# CF_ADC_Supply.net
KiCad netlist of a schematic drawn in Altium Designer
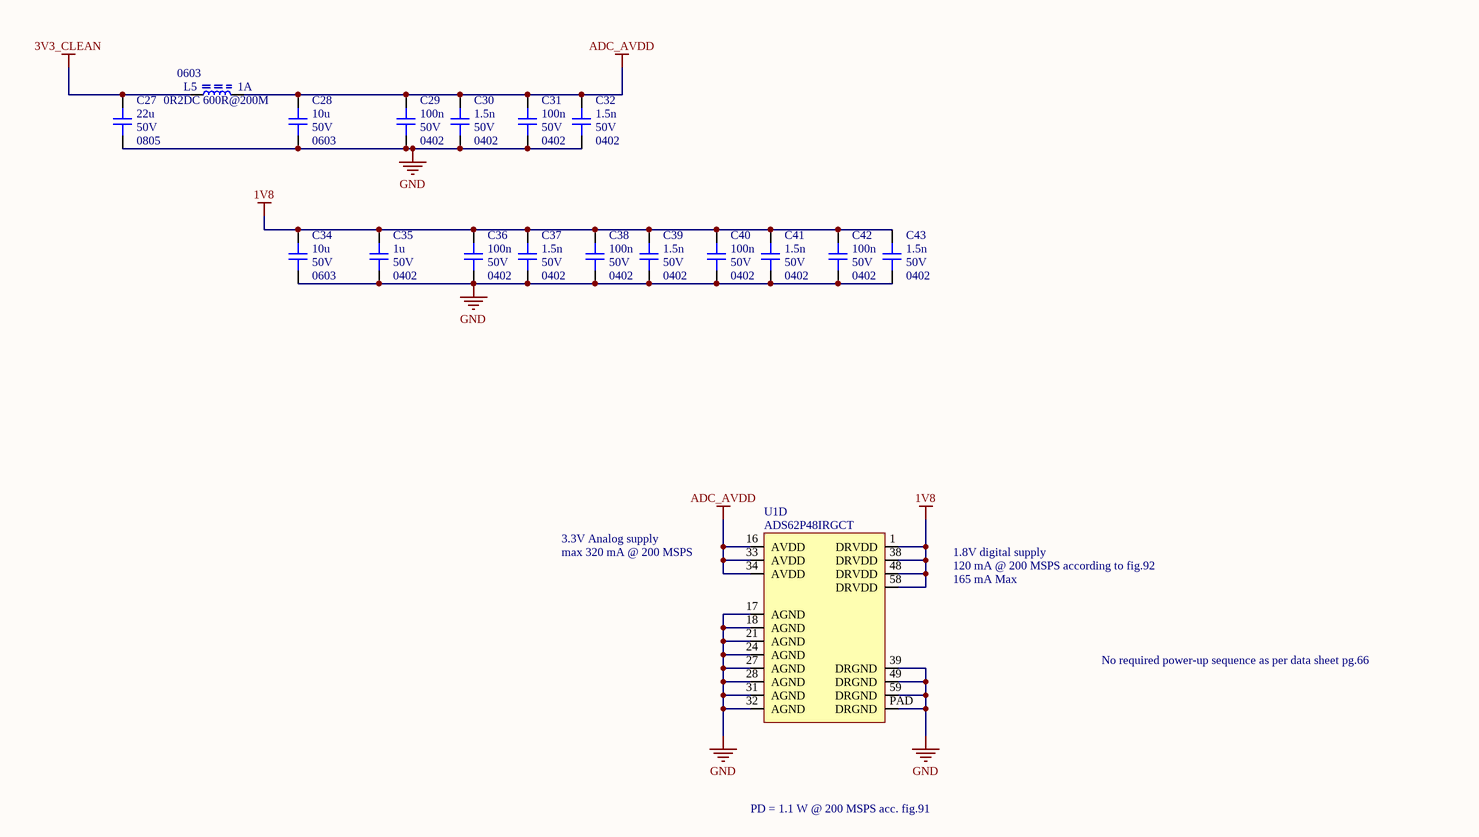
[diagram p0: CF_ADC_Supply.SchDoc]

(export (version "E")
  (design (tool "Eeschema 10.0.6"))
  (components
    (comp (ref "C27")
      (value "22u")
      (footprint "CAP_0805")
      (description "CAP - 0805")
      (fields
        (field (name "VOLTAGE") "50V")
        (field (name "PACKAGE") "0805")
        (field (name "CREATEDBY") "Jonathan Bouchard")
      )
      (libsource (lib "S7CAS_Lib2019_REV1_00") (part "CAP - 0805"))
    )
    (comp (ref "C28")
      (value "10u")
      (footprint "CAP_0603")
      (description "CAP - 0603")
      (fields
        (field (name "MFG PART NUMBER") "C1005X5R0J106M050BC")
        (field (name "VOLTAGE") "50V")
        (field (name "PACKAGE") "0603")
        (field (name "CREATEDBY") "Jonathan Bouchard")
      )
      (libsource (lib "S7CAS_Lib2019_REV1_00") (part "CAP - 0603"))
    )
    (comp (ref "C29")
      (value "100n")
      (footprint "CAP_0402")
      (description "CAP - 0402")
      (fields
        (field (name "MFG PART NUMBER") "C0603X5R1E104K030BB")
        (field (name "VOLTAGE") "50V")
        (field (name "PACKAGE") "0402")
        (field (name "CREATEDBY") "Jonathan Bouchard")
      )
      (libsource (lib "S7CAS_Lib2019_REV1_00") (part "CAP - 0402"))
    )
    (comp (ref "C30")
      (value "1.5n")
      (footprint "CAP_0402")
      (description "CAP - 0402")
      (fields
        (field (name "MFG PART NUMBER") "C0603X5R1E152M030BA")
        (field (name "VOLTAGE") "50V")
        (field (name "PACKAGE") "0402")
        (field (name "CREATEDBY") "Jonathan Bouchard")
      )
      (libsource (lib "S7CAS_Lib2019_REV1_00") (part "CAP - 0402"))
    )
    (comp (ref "C31")
      (value "100n")
      (footprint "CAP_0402")
      (description "CAP - 0402")
      (fields
        (field (name "MFG PART NUMBER") "C0603X5R1E104K030BB")
        (field (name "VOLTAGE") "50V")
        (field (name "PACKAGE") "0402")
        (field (name "CREATEDBY") "Jonathan Bouchard")
      )
      (libsource (lib "S7CAS_Lib2019_REV1_00") (part "CAP - 0402"))
    )
    (comp (ref "C32")
      (value "1.5n")
      (footprint "CAP_0402")
      (description "CAP - 0402")
      (fields
        (field (name "MFG PART NUMBER") "C0603X5R1E152M030BA")
        (field (name "VOLTAGE") "50V")
        (field (name "PACKAGE") "0402")
        (field (name "CREATEDBY") "Jonathan Bouchard")
      )
      (libsource (lib "S7CAS_Lib2019_REV1_00") (part "CAP - 0402"))
    )
    (comp (ref "C34")
      (value "10u")
      (footprint "CAP_0603")
      (description "CAP - 0603")
      (fields
        (field (name "MFG PART NUMBER") "C1005X5R0J106M050BC")
        (field (name "VOLTAGE") "50V")
        (field (name "PACKAGE") "0603")
        (field (name "CREATEDBY") "Jonathan Bouchard")
      )
      (libsource (lib "S7CAS_Lib2019_REV1_00") (part "CAP - 0603"))
    )
    (comp (ref "C35")
      (value "1u")
      (footprint "CAP_0402")
      (description "CAP - 0402")
      (fields
        (field (name "MFG PART NUMBER") "C0603X5R0J105M030BC")
        (field (name "VOLTAGE") "50V")
        (field (name "PACKAGE") "0402")
        (field (name "CREATEDBY") "Jonathan Bouchard")
      )
      (libsource (lib "S7CAS_Lib2019_REV1_00") (part "CAP - 0402"))
    )
    (comp (ref "C36")
      (value "100n")
      (footprint "CAP_0402")
      (description "CAP - 0402")
      (fields
        (field (name "MFG PART NUMBER") "C0603X5R1E104K030BB")
        (field (name "VOLTAGE") "50V")
        (field (name "PACKAGE") "0402")
        (field (name "CREATEDBY") "Jonathan Bouchard")
      )
      (libsource (lib "S7CAS_Lib2019_REV1_00") (part "CAP - 0402"))
    )
    (comp (ref "C37")
      (value "1.5n")
      (footprint "CAP_0402")
      (description "CAP - 0402")
      (fields
        (field (name "MFG PART NUMBER") "C0603X5R1E152M030BA")
        (field (name "VOLTAGE") "50V")
        (field (name "PACKAGE") "0402")
        (field (name "CREATEDBY") "Jonathan Bouchard")
      )
      (libsource (lib "S7CAS_Lib2019_REV1_00") (part "CAP - 0402"))
    )
    (comp (ref "C38")
      (value "100n")
      (footprint "CAP_0402")
      (description "CAP - 0402")
      (fields
        (field (name "MFG PART NUMBER") "C0603X5R1E104K030BB")
        (field (name "VOLTAGE") "50V")
        (field (name "PACKAGE") "0402")
        (field (name "CREATEDBY") "Jonathan Bouchard")
      )
      (libsource (lib "S7CAS_Lib2019_REV1_00") (part "CAP - 0402"))
    )
    (comp (ref "C39")
      (value "1.5n")
      (footprint "CAP_0402")
      (description "CAP - 0402")
      (fields
        (field (name "MFG PART NUMBER") "C0603X5R1E152M030BA")
        (field (name "VOLTAGE") "50V")
        (field (name "PACKAGE") "0402")
        (field (name "CREATEDBY") "Jonathan Bouchard")
      )
      (libsource (lib "S7CAS_Lib2019_REV1_00") (part "CAP - 0402"))
    )
    (comp (ref "C40")
      (value "100n")
      (footprint "CAP_0402")
      (description "CAP - 0402")
      (fields
        (field (name "MFG PART NUMBER") "C0603X5R1E104K030BB")
        (field (name "VOLTAGE") "50V")
        (field (name "PACKAGE") "0402")
        (field (name "CREATEDBY") "Jonathan Bouchard")
      )
      (libsource (lib "S7CAS_Lib2019_REV1_00") (part "CAP - 0402"))
    )
    (comp (ref "C41")
      (value "1.5n")
      (footprint "CAP_0402")
      (description "CAP - 0402")
      (fields
        (field (name "MFG PART NUMBER") "C0603X5R1E152M030BA")
        (field (name "VOLTAGE") "50V")
        (field (name "PACKAGE") "0402")
        (field (name "CREATEDBY") "Jonathan Bouchard")
      )
      (libsource (lib "S7CAS_Lib2019_REV1_00") (part "CAP - 0402"))
    )
    (comp (ref "C42")
      (value "100n")
      (footprint "CAP_0402")
      (description "CAP - 0402")
      (fields
        (field (name "MFG PART NUMBER") "C0603X5R1E104K030BB")
        (field (name "VOLTAGE") "50V")
        (field (name "PACKAGE") "0402")
        (field (name "CREATEDBY") "Jonathan Bouchard")
      )
      (libsource (lib "S7CAS_Lib2019_REV1_00") (part "CAP - 0402"))
    )
    (comp (ref "C43")
      (value "1.5n")
      (footprint "CAP_0402")
      (description "CAP - 0402")
      (fields
        (field (name "MFG PART NUMBER") "C0603X5R1E152M030BA")
        (field (name "VOLTAGE") "50V")
        (field (name "PACKAGE") "0402")
        (field (name "CREATEDBY") "Jonathan Bouchard")
      )
      (libsource (lib "S7CAS_Lib2019_REV1_00") (part "CAP - 0402"))
    )
    (comp (ref "L5")
      (value "0R2DC 600R@200M")
      (footprint "FER_0603")
      (description "FER - 0603")
      (fields
        (field (name "MFG") "Würth Elektronik")
        (field (name "MFG PART NUMBER") "782633601")
        (field (name "CURRENT") "1A")
        (field (name "PACKAGE") "0603")
        (field (name "CREATEDBY") "Jonathan Bouchard")
      )
      (libsource (lib "S7CAS_Lib2019_REV1_00") (part "FER - 0603"))
    )
    (comp (ref "U1")
      (value "ADS62P48IRGCT")
      (footprint "ADC_ADS62P48IRGCT")
      (description "ADC - 14 BIT 210MSPS SUAL - VQFN-64")
      (fields
        (field (name "VOLTAGE") "3.15 V ~ 3.6 V / 1.7 V ~ 1.9 V")
        (field (name "MFG") "Texas Instruments")
        (field (name "CREATEDBY") "Jonathan Bouchard")
      )
      (libsource (lib "S7CAS_Lib2019_REV1_00") (part "ADC_ADS62P48IRGCT"))
    )
  )
  (nets
    (net (code "1") (name "1V8") (class "Default")
      (node (ref "C34") (pin "2") (pinfunction "2_2") (pintype "passive"))
      (node (ref "C35") (pin "2") (pinfunction "2_2") (pintype "passive"))
      (node (ref "C36") (pin "2") (pinfunction "2_2") (pintype "passive"))
      (node (ref "C37") (pin "2") (pinfunction "2_2") (pintype "passive"))
      (node (ref "C38") (pin "2") (pinfunction "2_2") (pintype "passive"))
      (node (ref "C39") (pin "2") (pinfunction "2_2") (pintype "passive"))
      (node (ref "C40") (pin "2") (pinfunction "2_2") (pintype "passive"))
      (node (ref "C41") (pin "2") (pinfunction "2_2") (pintype "passive"))
      (node (ref "C42") (pin "2") (pinfunction "2_2") (pintype "passive"))
      (node (ref "C43") (pin "2") (pinfunction "2_2") (pintype "passive"))
      (node (ref "U1") (pin "1") (pinfunction "DRVDD_1") (pintype "passive"))
      (node (ref "U1") (pin "38") (pinfunction "DRVDD_38") (pintype "passive"))
      (node (ref "U1") (pin "48") (pinfunction "DRVDD_48") (pintype "passive"))
      (node (ref "U1") (pin "58") (pinfunction "DRVDD_58") (pintype "passive"))
    )
    (net (code "2") (name "3V3_CLEAN") (class "Default")
      (node (ref "C27") (pin "2") (pinfunction "2_2") (pintype "passive"))
      (node (ref "L5") (pin "2") (pinfunction "2_2") (pintype "passive"))
    )
    (net (code "3") (name "ADC_AVDD") (class "Default")
      (node (ref "C28") (pin "2") (pinfunction "2_2") (pintype "passive"))
      (node (ref "C29") (pin "2") (pinfunction "2_2") (pintype "passive"))
      (node (ref "C30") (pin "2") (pinfunction "2_2") (pintype "passive"))
      (node (ref "C31") (pin "2") (pinfunction "2_2") (pintype "passive"))
      (node (ref "C32") (pin "2") (pinfunction "2_2") (pintype "passive"))
      (node (ref "L5") (pin "1") (pinfunction "1_1") (pintype "passive"))
      (node (ref "U1") (pin "16") (pinfunction "AVDD_16") (pintype "passive"))
      (node (ref "U1") (pin "33") (pinfunction "AVDD_33") (pintype "passive"))
      (node (ref "U1") (pin "34") (pinfunction "AVDD_34") (pintype "passive"))
    )
    (net (code "4") (name "GND") (class "Default")
      (node (ref "C27") (pin "1") (pinfunction "1_1") (pintype "passive"))
      (node (ref "C28") (pin "1") (pinfunction "1_1") (pintype "passive"))
      (node (ref "C29") (pin "1") (pinfunction "1_1") (pintype "passive"))
      (node (ref "C30") (pin "1") (pinfunction "1_1") (pintype "passive"))
      (node (ref "C31") (pin "1") (pinfunction "1_1") (pintype "passive"))
      (node (ref "C32") (pin "1") (pinfunction "1_1") (pintype "passive"))
      (node (ref "C34") (pin "1") (pinfunction "1_1") (pintype "passive"))
      (node (ref "C35") (pin "1") (pinfunction "1_1") (pintype "passive"))
      (node (ref "C36") (pin "1") (pinfunction "1_1") (pintype "passive"))
      (node (ref "C37") (pin "1") (pinfunction "1_1") (pintype "passive"))
      (node (ref "C38") (pin "1") (pinfunction "1_1") (pintype "passive"))
      (node (ref "C39") (pin "1") (pinfunction "1_1") (pintype "passive"))
      (node (ref "C40") (pin "1") (pinfunction "1_1") (pintype "passive"))
      (node (ref "C41") (pin "1") (pinfunction "1_1") (pintype "passive"))
      (node (ref "C42") (pin "1") (pinfunction "1_1") (pintype "passive"))
      (node (ref "C43") (pin "1") (pinfunction "1_1") (pintype "passive"))
      (node (ref "U1") (pin "17") (pinfunction "AGND_17") (pintype "passive"))
      (node (ref "U1") (pin "18") (pinfunction "AGND_18") (pintype "passive"))
      (node (ref "U1") (pin "21") (pinfunction "AGND_21") (pintype "passive"))
      (node (ref "U1") (pin "24") (pinfunction "AGND_24") (pintype "passive"))
      (node (ref "U1") (pin "27") (pinfunction "AGND_27") (pintype "passive"))
      (node (ref "U1") (pin "28") (pinfunction "AGND_28") (pintype "passive"))
      (node (ref "U1") (pin "31") (pinfunction "AGND_31") (pintype "passive"))
      (node (ref "U1") (pin "32") (pinfunction "AGND_32") (pintype "passive"))
      (node (ref "U1") (pin "39") (pinfunction "DRGND_39") (pintype "passive"))
      (node (ref "U1") (pin "49") (pinfunction "DRGND_49") (pintype "passive"))
      (node (ref "U1") (pin "59") (pinfunction "DRGND_59") (pintype "passive"))
      (node (ref "U1") (pin "PAD") (pinfunction "DRGND_PAD") (pintype "passive"))
    )
  )
)
